# H18R11.net
KiCad netlist of a schematic drawn in EAGLE
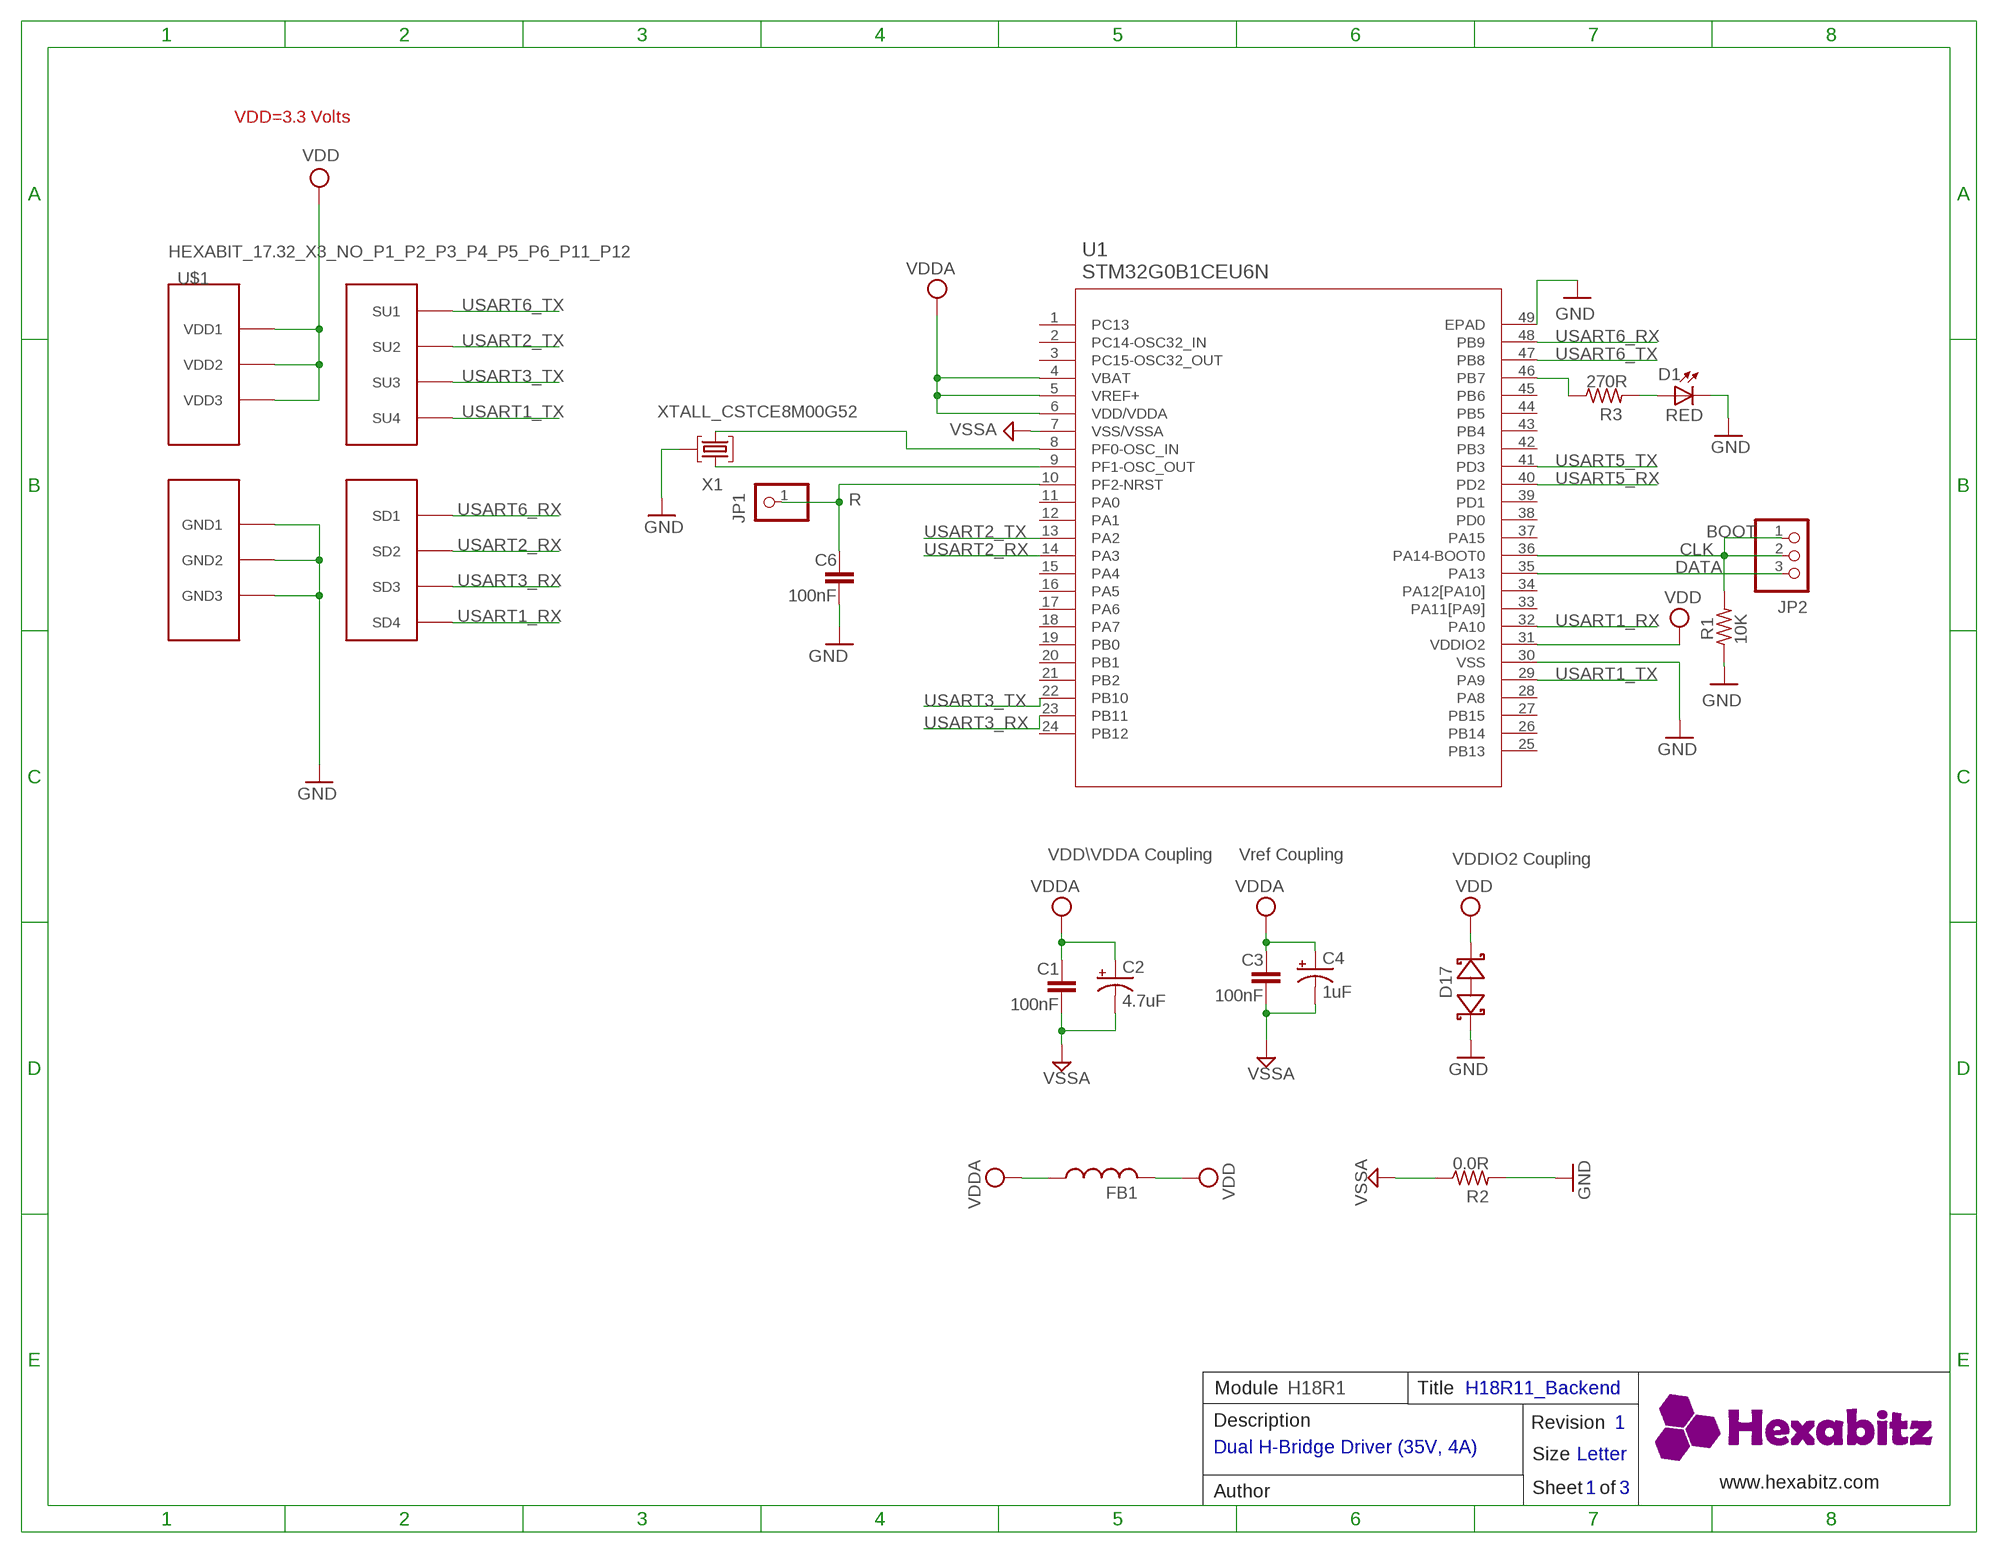
[diagram p0: schematic, sheet 1]
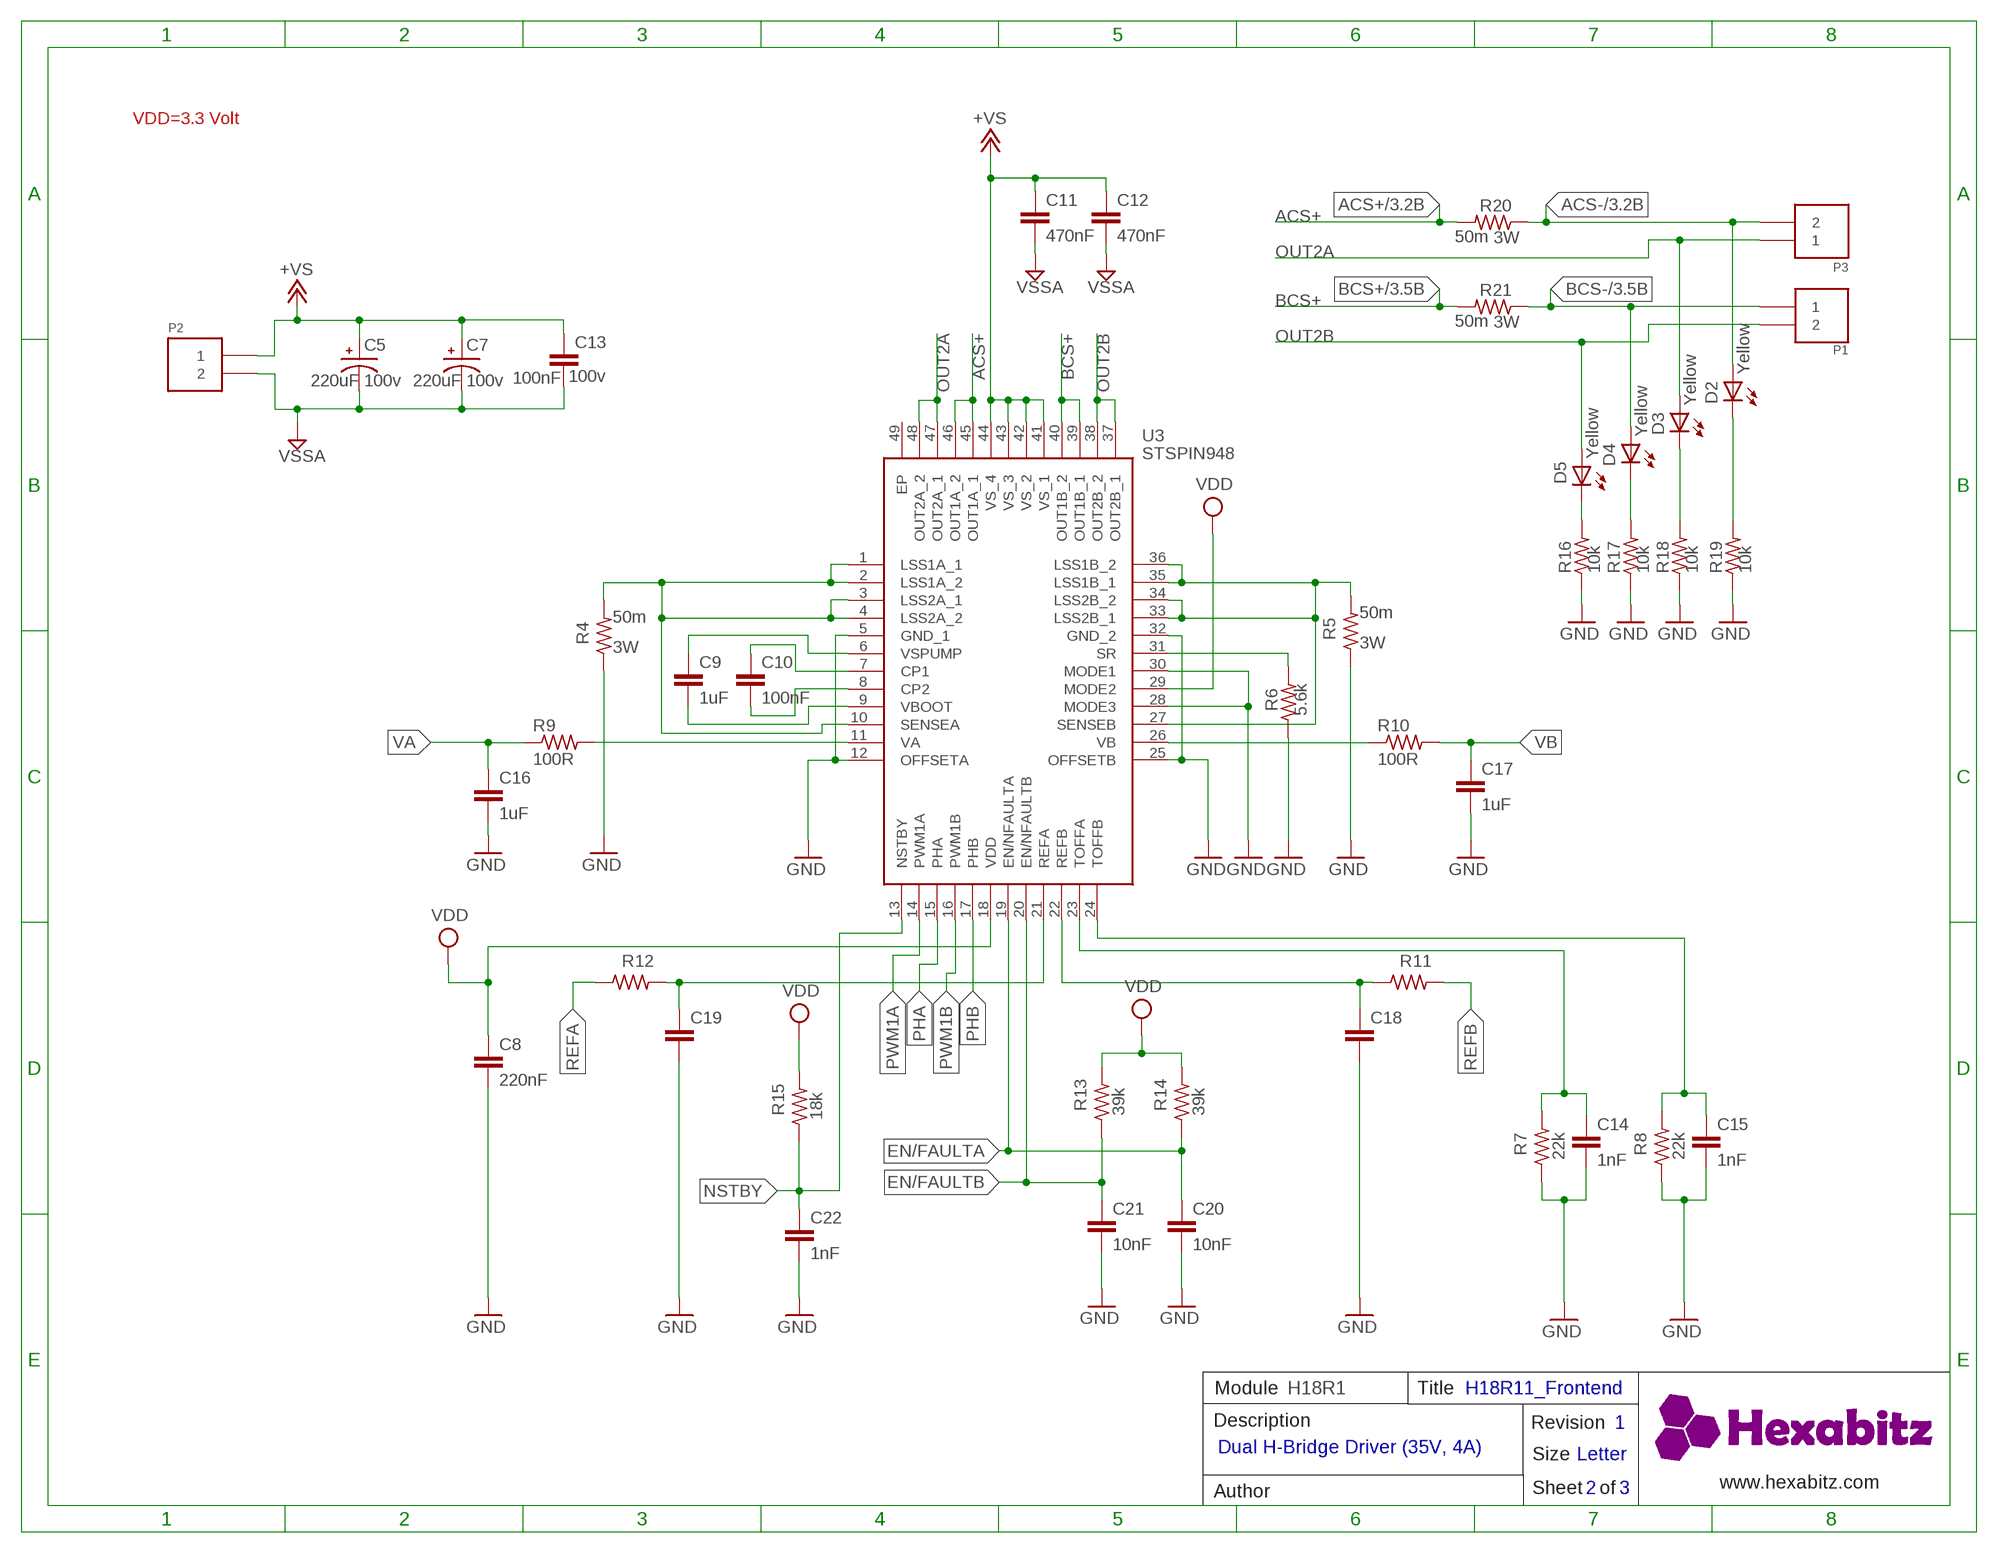
[diagram p1: schematic, sheet 2]
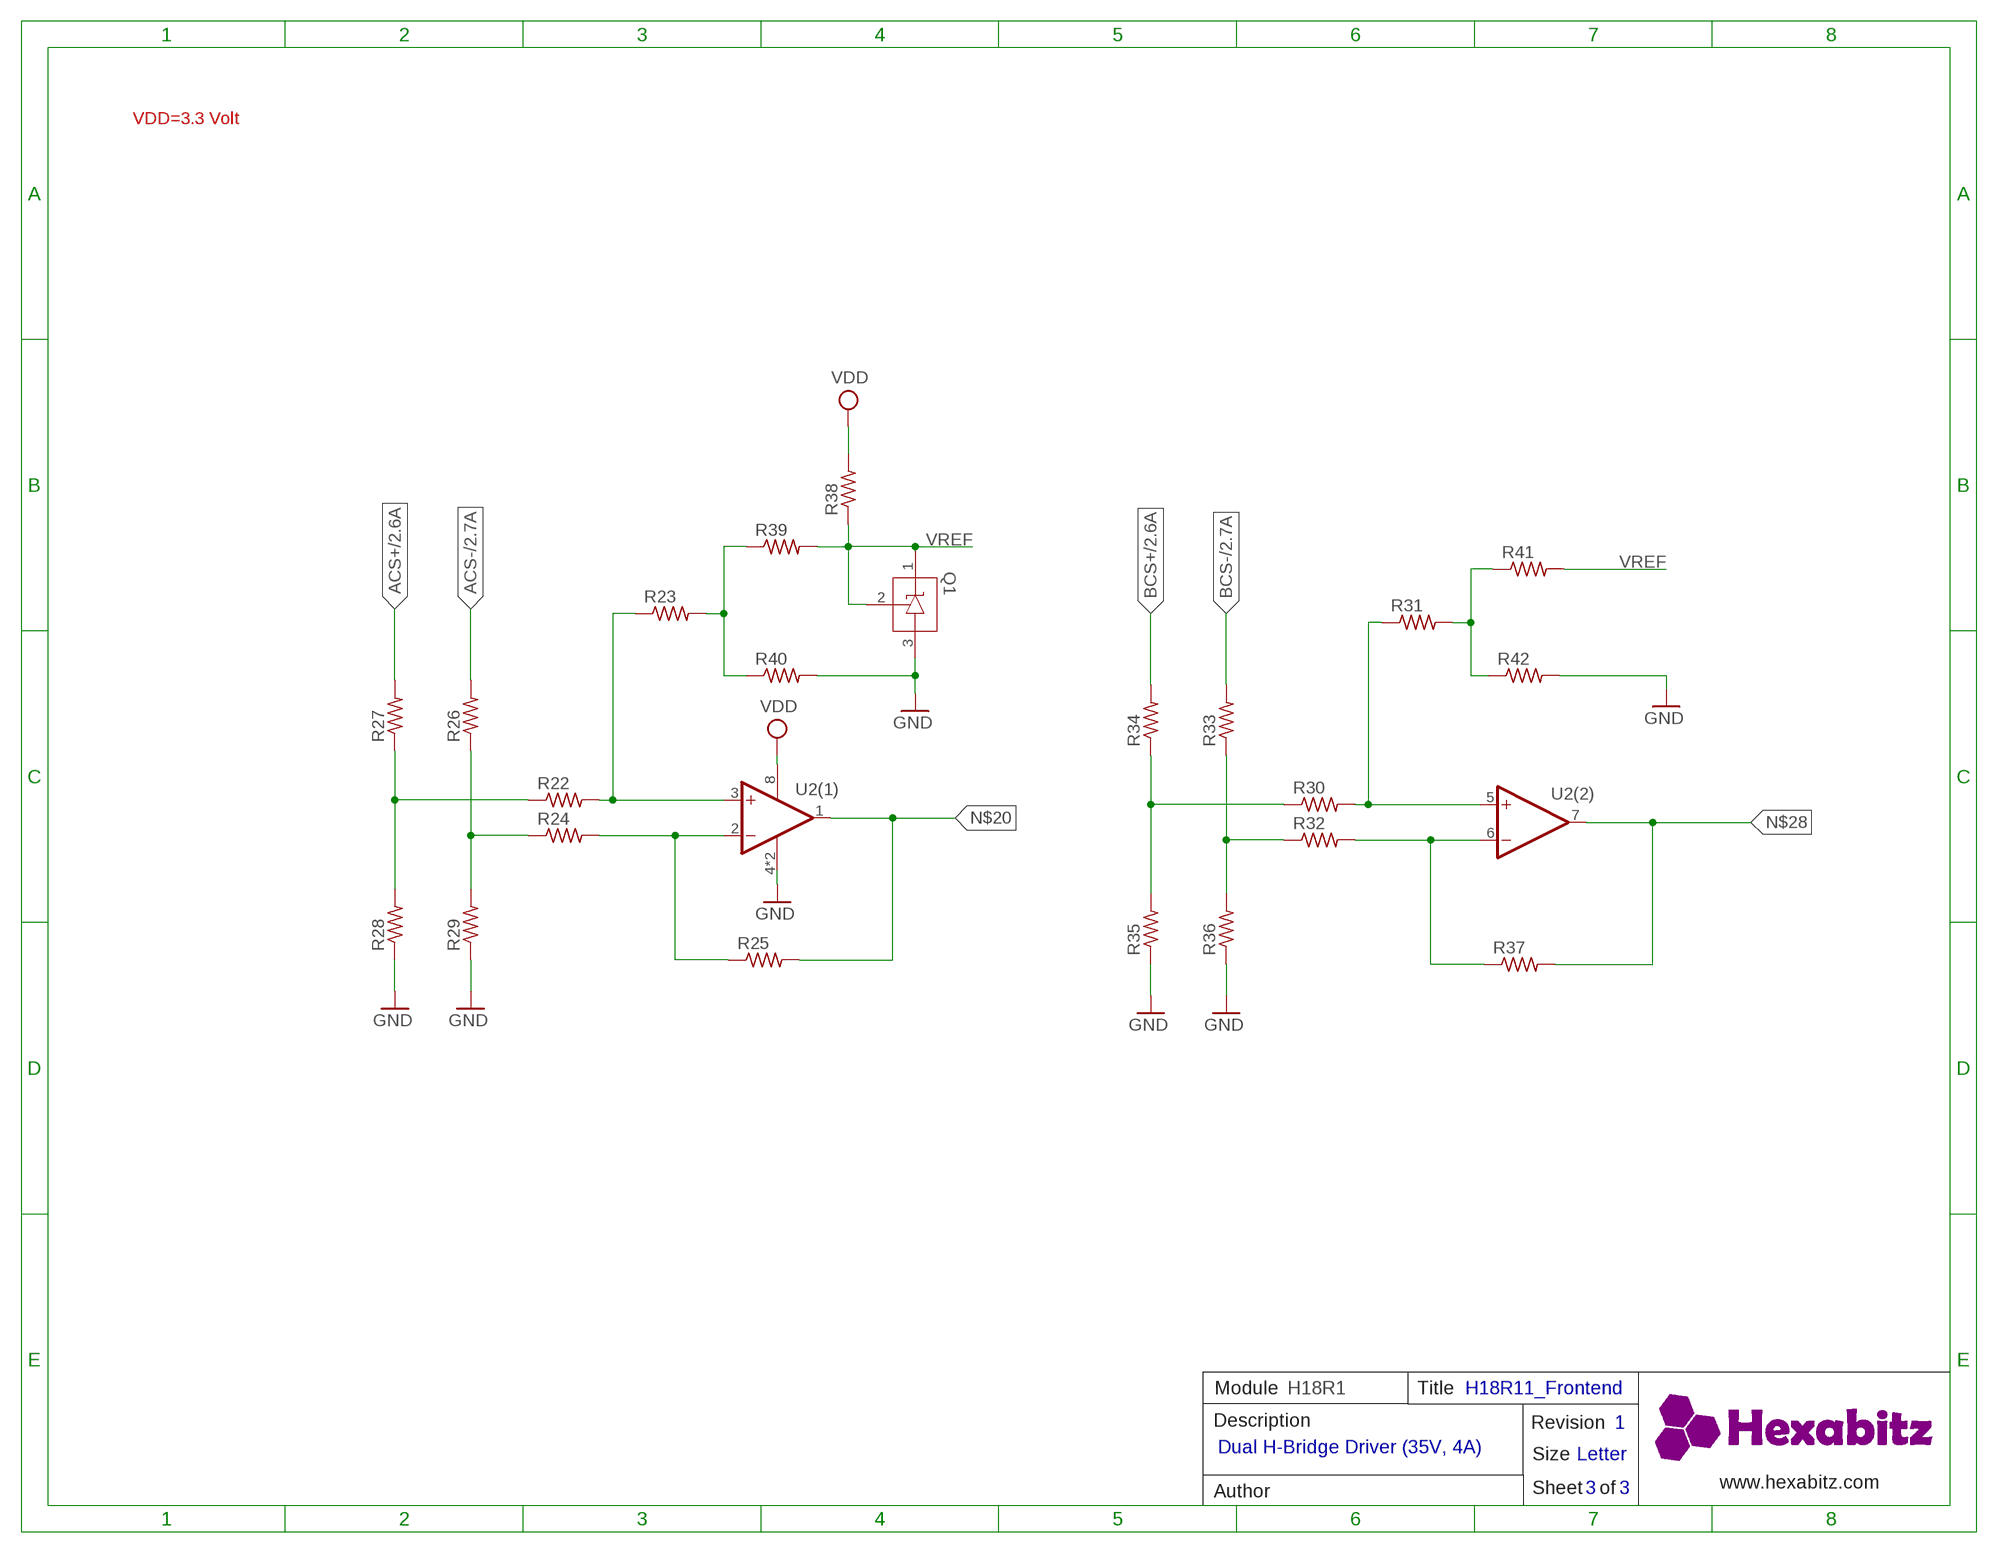
[diagram p2: schematic, sheet 3]

(export (version "E")
  (design (tool "Eeschema 10.0.6"))
  (components
    (comp (ref "Q1")
      (value "TL431QDBZR,215")
      (footprint "eagle-import:SOT23_TO-236AB_NEX")
      (fields (field (name "COPYRIGHT") "Copyright (C) 2022 Ultra Librarian. All rights reserved."))
      (libsource (lib "eagle-import") (part "TL431QDBZR,215"))
    )
    (comp (ref "R22")
      (value "R-0402")
      (footprint "eagle-import:R-0402")
      (libsource (lib "eagle-import") (part "R-0402"))
    )
    (comp (ref "R23")
      (value "R-0402")
      (footprint "eagle-import:R-0402")
      (libsource (lib "eagle-import") (part "R-0402"))
    )
    (comp (ref "R24")
      (value "R-0402")
      (footprint "eagle-import:R-0402")
      (libsource (lib "eagle-import") (part "R-0402"))
    )
    (comp (ref "R25")
      (value "R-0402")
      (footprint "eagle-import:R-0402")
      (libsource (lib "eagle-import") (part "R-0402"))
    )
    (comp (ref "R26")
      (value "R-0402")
      (footprint "eagle-import:R-0402")
      (libsource (lib "eagle-import") (part "R-0402"))
    )
    (comp (ref "R27")
      (value "R-0402")
      (footprint "eagle-import:R-0402")
      (libsource (lib "eagle-import") (part "R-0402"))
    )
    (comp (ref "R28")
      (value "R-0402")
      (footprint "eagle-import:R-0402")
      (libsource (lib "eagle-import") (part "R-0402"))
    )
    (comp (ref "R29")
      (value "R-0402")
      (footprint "eagle-import:R-0402")
      (libsource (lib "eagle-import") (part "R-0402"))
    )
    (comp (ref "R30")
      (value "R-0402")
      (footprint "eagle-import:R-0402")
      (libsource (lib "eagle-import") (part "R-0402"))
    )
    (comp (ref "R31")
      (value "R-0402")
      (footprint "eagle-import:R-0402")
      (libsource (lib "eagle-import") (part "R-0402"))
    )
    (comp (ref "R32")
      (value "R-0402")
      (footprint "eagle-import:R-0402")
      (libsource (lib "eagle-import") (part "R-0402"))
    )
    (comp (ref "R33")
      (value "R-0402")
      (footprint "eagle-import:R-0402")
      (libsource (lib "eagle-import") (part "R-0402"))
    )
    (comp (ref "R34")
      (value "R-0402")
      (footprint "eagle-import:R-0402")
      (libsource (lib "eagle-import") (part "R-0402"))
    )
    (comp (ref "R35")
      (value "R-0402")
      (footprint "eagle-import:R-0402")
      (libsource (lib "eagle-import") (part "R-0402"))
    )
    (comp (ref "R36")
      (value "R-0402")
      (footprint "eagle-import:R-0402")
      (libsource (lib "eagle-import") (part "R-0402"))
    )
    (comp (ref "R37")
      (value "R-0402")
      (footprint "eagle-import:R-0402")
      (libsource (lib "eagle-import") (part "R-0402"))
    )
    (comp (ref "R38")
      (value "R-0402")
      (footprint "eagle-import:R-0402")
      (libsource (lib "eagle-import") (part "R-0402"))
    )
    (comp (ref "R39")
      (value "R-0402")
      (footprint "eagle-import:R-0402")
      (libsource (lib "eagle-import") (part "R-0402"))
    )
    (comp (ref "R40")
      (value "R-0402")
      (footprint "eagle-import:R-0402")
      (libsource (lib "eagle-import") (part "R-0402"))
    )
    (comp (ref "R41")
      (value "R-0402")
      (footprint "eagle-import:R-0402")
      (libsource (lib "eagle-import") (part "R-0402"))
    )
    (comp (ref "R42")
      (value "R-0402")
      (footprint "eagle-import:R-0402")
      (libsource (lib "eagle-import") (part "R-0402"))
    )
    (comp (ref "U2")
      (value "TSV772IQ2T_SEPARATED_SYMBOLSSON50P200X200X60-9N")
      (footprint "eagle-import:SON50P200X200X60-9N")
      (libsource (lib "eagle-import") (part "TSV772IQ2T_SEPARATED_SYMBOLSSON50P200X200X60-9N"))
    )
    (comp (ref "C1")
      (value "100nF")
      (footprint "eagle-import:C-0603")
      (libsource (lib "eagle-import") (part "C-0603"))
    )
    (comp (ref "C2")
      (value "4.7uF")
      (footprint "eagle-import:C-0805-POL")
      (libsource (lib "eagle-import") (part "C-0805-POL"))
    )
    (comp (ref "C3")
      (value "100nF")
      (footprint "eagle-import:C-0603")
      (libsource (lib "eagle-import") (part "C-0603"))
    )
    (comp (ref "C4")
      (value "1uF")
      (footprint "eagle-import:C-0805-POL")
      (libsource (lib "eagle-import") (part "C-0805-POL"))
    )
    (comp (ref "C6")
      (value "100nF")
      (footprint "eagle-import:C-0603")
      (libsource (lib "eagle-import") (part "C-0603"))
    )
    (comp (ref "D1")
      (value "RED")
      (footprint "eagle-import:VLMS1300-GS08")
      (fields
        (field (name "MPN") "VLMS1300-GS08")
        (field (name "MFN") "Vishay")
        (field (name "MPN_1") "VLMS1300-GS08")
        (field (name "OCTOPART_URL") "https://octopart.com/vlms1300-gs08-vishay-21709201?r=sp&s=_gcP4_q8T1SC6PJQPTQ9yA")
      )
      (libsource (lib "eagle-import") (part "VLMS1300-GS08"))
    )
    (comp (ref "D17")
      (value "BOURNS_CDSOD323-T03SCBOURNS_CDSOD323-T03SC_0_0")
      (footprint "eagle-import:BOURNS_CDSOD323-T03SC_0")
      (fields (field (name "MPN") "CDSOD323-T03SC"))
      (libsource (lib "eagle-import") (part "BOURNS_CDSOD323-T03SCBOURNS_CDSOD323-T03SC_0_0"))
    )
    (comp (ref "FB1")
      (value "FB-0603")
      (footprint "eagle-import:FB-0603")
      (libsource (lib "eagle-import") (part "FB-0603"))
    )
    (comp (ref "JP1")
      (value "R")
      (footprint "eagle-import:1X01")
      (fields (field (name "MPN") "87227-1"))
      (libsource (lib "eagle-import") (part "PINHD-1X1"))
    )
    (comp (ref "JP2")
      (value "PINHD-1X3")
      (footprint "eagle-import:1X03")
      (libsource (lib "eagle-import") (part "PINHD-1X3"))
    )
    (comp (ref "R1")
      (value "10K")
      (footprint "eagle-import:R-0603")
      (libsource (lib "eagle-import") (part "R-0603"))
    )
    (comp (ref "R2")
      (value "0.0R")
      (footprint "eagle-import:R-0603")
      (libsource (lib "eagle-import") (part "R-0603"))
    )
    (comp (ref "R3")
      (value "270R")
      (footprint "eagle-import:R-0603")
      (libsource (lib "eagle-import") (part "R-0603"))
    )
    (comp (ref "U$1")
      (value "HEXABIT_17.32_X3_NO_P1_P2_P3_P4_P5_P6_P11_P12")
      (footprint "eagle-import:HEXABIT_17.32_X3_NO_P1_P2_P3_P4_P5_P6_P11_P12")
      (libsource (lib "eagle-import") (part "HEXABIT_17.32_X3_NO_P1_P2_P3_P4_P5_P6_P11_P12"))
    )
    (comp (ref "U1")
      (value "STM32G0B1CEU6N")
      (footprint "eagle-import:HEXABITZ_ICS_QFN_B1CEU6_STM-L")
      (libsource (lib "eagle-import") (part "STM32G0B1CEU6N"))
    )
    (comp (ref "X1")
      (value "XTALL_CSTCE8M00G52")
      (footprint "eagle-import:XTALL_CSTCE8M00G52")
      (fields (field (name "MPN") "CSTCE8M00G52Z-R0"))
      (libsource (lib "eagle-import") (part "XTALL_CSTCE8M00G52"))
    )
    (comp (ref "C5")
      (value "220uF")
      (footprint "eagle-import:CAPPRD500W60D1250H2500")
      (fields
        (field (name "MF") "Panasonic Electronic Components")
        (field (name "MP") "EEU-FS2A221B")
        (field (name "VOLT") "100v")
      )
      (libsource (lib "eagle-import") (part "EEUFS2A221B"))
    )
    (comp (ref "C7")
      (value "220uF")
      (footprint "eagle-import:CAPPRD500W60D1250H2500")
      (fields
        (field (name "MF") "Panasonic Electronic Components")
        (field (name "MP") "EEU-FS2A221B")
        (field (name "VOLT") "100v")
      )
      (libsource (lib "eagle-import") (part "EEUFS2A221B"))
    )
    (comp (ref "C8")
      (value "220nF")
      (footprint "eagle-import:C-0603")
      (libsource (lib "eagle-import") (part "C-0603"))
    )
    (comp (ref "C9")
      (value "1uF")
      (footprint "eagle-import:C-0603")
      (libsource (lib "eagle-import") (part "C-0603"))
    )
    (comp (ref "C10")
      (value "100nF")
      (footprint "eagle-import:C-0603")
      (libsource (lib "eagle-import") (part "C-0603"))
    )
    (comp (ref "C11")
      (value "470nF")
      (footprint "eagle-import:C-0603")
      (libsource (lib "eagle-import") (part "C-0603"))
    )
    (comp (ref "C12")
      (value "470nF")
      (footprint "eagle-import:C-0603")
      (libsource (lib "eagle-import") (part "C-0603"))
    )
    (comp (ref "C13")
      (value "100nF")
      (footprint "eagle-import:C-0603")
      (fields (field (name "VOLTAGE_RATING") "100v"))
      (libsource (lib "eagle-import") (part "C-0603"))
    )
    (comp (ref "C14")
      (value "1nF")
      (footprint "eagle-import:C-0603")
      (libsource (lib "eagle-import") (part "C-0603"))
    )
    (comp (ref "C15")
      (value "1nF")
      (footprint "eagle-import:C-0603")
      (libsource (lib "eagle-import") (part "C-0603"))
    )
    (comp (ref "C16")
      (value "1uF")
      (footprint "eagle-import:C-0603")
      (libsource (lib "eagle-import") (part "C-0603"))
    )
    (comp (ref "C17")
      (value "1uF")
      (footprint "eagle-import:C-0603")
      (libsource (lib "eagle-import") (part "C-0603"))
    )
    (comp (ref "C18")
      (value "C-0603")
      (footprint "eagle-import:C-0603")
      (libsource (lib "eagle-import") (part "C-0603"))
    )
    (comp (ref "C19")
      (value "C-0603")
      (footprint "eagle-import:C-0603")
      (libsource (lib "eagle-import") (part "C-0603"))
    )
    (comp (ref "C20")
      (value "10nF")
      (footprint "eagle-import:C-0603")
      (libsource (lib "eagle-import") (part "C-0603"))
    )
    (comp (ref "C21")
      (value "10nF")
      (footprint "eagle-import:C-0603")
      (libsource (lib "eagle-import") (part "C-0603"))
    )
    (comp (ref "C22")
      (value "1nF")
      (footprint "eagle-import:C-0603")
      (libsource (lib "eagle-import") (part "C-0603"))
    )
    (comp (ref "D2")
      (value "Yellow")
      (footprint "eagle-import:VLMS1300-GS08")
      (fields
        (field (name "MPN") "VLMS1300-GS08")
        (field (name "MFN") "Vishay")
        (field (name "MPN_1") "VLMS1300-GS08")
        (field (name "OCTOPART_URL") "https://octopart.com/vlms1300-gs08-vishay-21709201?r=sp&s=_gcP4_q8T1SC6PJQPTQ9yA")
      )
      (libsource (lib "eagle-import") (part "VLMS1300-GS08"))
    )
    (comp (ref "D3")
      (value "Yellow")
      (footprint "eagle-import:VLMS1300-GS08")
      (fields
        (field (name "MPN") "VLMS1300-GS08")
        (field (name "OCTOPART_URL") "https://octopart.com/vlms1300-gs08-vishay-21709201?r=sp&s=_gcP4_q8T1SC6PJQPTQ9yA")
      )
      (libsource (lib "eagle-import") (part "VLMS1300-GS08"))
    )
    (comp (ref "D4")
      (value "Yellow")
      (footprint "eagle-import:VLMS1300-GS08")
      (fields
        (field (name "MPN") "VLMS1300-GS08")
        (field (name "OCTOPART_URL") "https://octopart.com/vlms1300-gs08-vishay-21709201?r=sp&s=_gcP4_q8T1SC6PJQPTQ9yA")
      )
      (libsource (lib "eagle-import") (part "VLMS1300-GS08"))
    )
    (comp (ref "D5")
      (value "Yellow")
      (footprint "eagle-import:VLMS1300-GS08")
      (fields
        (field (name "MPN") "VLMS1300-GS08")
        (field (name "OCTOPART_URL") "https://octopart.com/vlms1300-gs08-vishay-21709201?r=sp&s=_gcP4_q8T1SC6PJQPTQ9yA")
      )
      (libsource (lib "eagle-import") (part "VLMS1300-GS08"))
    )
    (comp (ref "P1")
      (value "1546111-2")
      (footprint "eagle-import:1546111-2")
      (libsource (lib "eagle-import") (part "1546111-2"))
    )
    (comp (ref "P2")
      (value "1546111-2")
      (footprint "eagle-import:1546111-2")
      (libsource (lib "eagle-import") (part "1546111-2"))
    )
    (comp (ref "P3")
      (value "1546111-2")
      (footprint "eagle-import:1546111-2")
      (libsource (lib "eagle-import") (part "1546111-2"))
    )
    (comp (ref "R4")
      (value "50m")
      (footprint "eagle-import:R2512")
      (fields (field (name "MPN") "CRA2512-FZ-R050ELF ") (field (name "POWER") "3W"))
      (libsource (lib "eagle-import") (part "R-US_R2512"))
    )
    (comp (ref "R5")
      (value "50m")
      (footprint "eagle-import:R2512")
      (fields (field (name "MPN") "CRA2512-FZ-R050ELF ") (field (name "POWER") "3W"))
      (libsource (lib "eagle-import") (part "R-US_R2512"))
    )
    (comp (ref "R6")
      (value "5.6k")
      (footprint "eagle-import:R-0603")
      (libsource (lib "eagle-import") (part "R-0603"))
    )
    (comp (ref "R7")
      (value "22k")
      (footprint "eagle-import:R-0603")
      (libsource (lib "eagle-import") (part "R-0603"))
    )
    (comp (ref "R8")
      (value "22k")
      (footprint "eagle-import:R-0603")
      (libsource (lib "eagle-import") (part "R-0603"))
    )
    (comp (ref "R9")
      (value "100R")
      (footprint "eagle-import:R-0603")
      (libsource (lib "eagle-import") (part "R-0603"))
    )
    (comp (ref "R10")
      (value "100R")
      (footprint "eagle-import:R-0603")
      (libsource (lib "eagle-import") (part "R-0603"))
    )
    (comp (ref "R11")
      (value "R-0603")
      (footprint "eagle-import:R-0603")
      (libsource (lib "eagle-import") (part "R-0603"))
    )
    (comp (ref "R12")
      (value "R-0603")
      (footprint "eagle-import:R-0603")
      (libsource (lib "eagle-import") (part "R-0603"))
    )
    (comp (ref "R13")
      (value "39k")
      (footprint "eagle-import:R-0603")
      (libsource (lib "eagle-import") (part "R-0603"))
    )
    (comp (ref "R14")
      (value "39k")
      (footprint "eagle-import:R-0603")
      (libsource (lib "eagle-import") (part "R-0603"))
    )
    (comp (ref "R15")
      (value "18k")
      (footprint "eagle-import:R-0603")
      (libsource (lib "eagle-import") (part "R-0603"))
    )
    (comp (ref "R16")
      (value "10k")
      (footprint "eagle-import:R-0805")
      (libsource (lib "eagle-import") (part "R-0805"))
    )
    (comp (ref "R17")
      (value "10k")
      (footprint "eagle-import:R-0805")
      (libsource (lib "eagle-import") (part "R-0805"))
    )
    (comp (ref "R18")
      (value "10k")
      (footprint "eagle-import:R-0805")
      (libsource (lib "eagle-import") (part "R-0805"))
    )
    (comp (ref "R19")
      (value "10k")
      (footprint "eagle-import:R-0805")
      (libsource (lib "eagle-import") (part "R-0805"))
    )
    (comp (ref "R20")
      (value "50m")
      (footprint "eagle-import:R2512")
      (fields (field (name "MPN") "CRA2512-FZ-R050ELF ") (field (name "POWER") "3W"))
      (libsource (lib "eagle-import") (part "R-US_R2512"))
    )
    (comp (ref "R21")
      (value "50m")
      (footprint "eagle-import:R2512")
      (fields (field (name "MPN") "CRA2512-FZ-R050ELF ") (field (name "POWER") "3W"))
      (libsource (lib "eagle-import") (part "R-US_R2512"))
    )
    (comp (ref "U3")
      (value "STSPIN948")
      (footprint "eagle-import:QFN50P700X700X105-49N")
      (fields (field (name "MOUSER_PART_NUMBER") "511-STSPIN948"))
      (libsource (lib "eagle-import") (part "STSPIN948"))
    )
  )
  (nets
    (net (code "1") (name "+VS") (class "Default")
      (node (ref "C11") (pin "1") (pinfunction "1_1") (pintype "passive"))
      (node (ref "C12") (pin "1") (pinfunction "1_1") (pintype "passive"))
      (node (ref "C13") (pin "1") (pinfunction "1_1") (pintype "passive"))
      (node (ref "C5") (pin "P") (pinfunction "P_P") (pintype "passive"))
      (node (ref "C7") (pin "P") (pinfunction "P_P") (pintype "passive"))
      (node (ref "P2") (pin "1") (pinfunction "1_1") (pintype "power_in"))
      (node (ref "U3") (pin "41") (pinfunction "VS_1_41") (pintype "bidirectional"))
      (node (ref "U3") (pin "42") (pinfunction "VS_2_42") (pintype "bidirectional"))
      (node (ref "U3") (pin "43") (pinfunction "VS_3_43") (pintype "bidirectional"))
      (node (ref "U3") (pin "44") (pinfunction "VS_4_44") (pintype "bidirectional"))
    )
    (net (code "2") (name "ACS+") (class "Default")
      (node (ref "R20") (pin "2") (pinfunction "2_2") (pintype "passive"))
      (node (ref "R27") (pin "2") (pinfunction "2_2") (pintype "passive"))
      (node (ref "U3") (pin "45") (pinfunction "OUT1A_1_45") (pintype "bidirectional"))
      (node (ref "U3") (pin "46") (pinfunction "OUT1A_2_46") (pintype "bidirectional"))
    )
    (net (code "3") (name "ACS-") (class "Default")
      (node (ref "D2") (pin "A") (pinfunction "A_A") (pintype "passive"))
      (node (ref "P3") (pin "2") (pinfunction "2_2") (pintype "power_in"))
      (node (ref "R20") (pin "1") (pinfunction "1_1") (pintype "passive"))
      (node (ref "R26") (pin "2") (pinfunction "2_2") (pintype "passive"))
    )
    (net (code "4") (name "BCS+") (class "Default")
      (node (ref "R21") (pin "2") (pinfunction "2_2") (pintype "passive"))
      (node (ref "R34") (pin "2") (pinfunction "2_2") (pintype "passive"))
      (node (ref "U3") (pin "39") (pinfunction "OUT1B_1_39") (pintype "bidirectional"))
      (node (ref "U3") (pin "40") (pinfunction "OUT1B_2_40") (pintype "bidirectional"))
    )
    (net (code "5") (name "BCS-") (class "Default")
      (node (ref "D4") (pin "A") (pinfunction "A_A") (pintype "passive"))
      (node (ref "P1") (pin "1") (pinfunction "1_1") (pintype "power_in"))
      (node (ref "R21") (pin "1") (pinfunction "1_1") (pintype "passive"))
      (node (ref "R33") (pin "2") (pinfunction "2_2") (pintype "passive"))
    )
    (net (code "6") (name "CLK") (class "Default")
      (node (ref "JP2") (pin "1") (pinfunction "1_1") (pintype "passive"))
      (node (ref "JP2") (pin "2") (pinfunction "2_2") (pintype "passive"))
      (node (ref "R1") (pin "2") (pinfunction "2_2") (pintype "passive"))
      (node (ref "U1") (pin "36") (pinfunction "PA14-BOOT0_36") (pintype "bidirectional"))
    )
    (net (code "7") (name "DATA") (class "Default")
      (node (ref "JP2") (pin "3") (pinfunction "3_3") (pintype "passive"))
      (node (ref "U1") (pin "35") (pinfunction "PA13_35") (pintype "bidirectional"))
    )
    (net (code "8") (name "EN{slash}FAULTA") (class "Default")
      (node (ref "C20") (pin "1") (pinfunction "1_1") (pintype "passive"))
      (node (ref "R14") (pin "1") (pinfunction "1_1") (pintype "passive"))
      (node (ref "U3") (pin "19") (pinfunction "EN/NFAULTA_19") (pintype "bidirectional"))
    )
    (net (code "9") (name "EN{slash}FAULTB") (class "Default")
      (node (ref "C21") (pin "1") (pinfunction "1_1") (pintype "passive"))
      (node (ref "R13") (pin "1") (pinfunction "1_1") (pintype "passive"))
      (node (ref "U3") (pin "20") (pinfunction "EN/NFAULTB_20") (pintype "bidirectional"))
    )
    (net (code "10") (name "GND") (class "Default")
      (node (ref "C14") (pin "2") (pinfunction "2_2") (pintype "passive"))
      (node (ref "C15") (pin "2") (pinfunction "2_2") (pintype "passive"))
      (node (ref "C16") (pin "2") (pinfunction "2_2") (pintype "passive"))
      (node (ref "C17") (pin "2") (pinfunction "2_2") (pintype "passive"))
      (node (ref "C18") (pin "2") (pinfunction "2_2") (pintype "passive"))
      (node (ref "C19") (pin "2") (pinfunction "2_2") (pintype "passive"))
      (node (ref "C20") (pin "2") (pinfunction "2_2") (pintype "passive"))
      (node (ref "C21") (pin "2") (pinfunction "2_2") (pintype "passive"))
      (node (ref "C22") (pin "2") (pinfunction "2_2") (pintype "passive"))
      (node (ref "C6") (pin "2") (pinfunction "2_2") (pintype "passive"))
      (node (ref "C8") (pin "2") (pinfunction "2_2") (pintype "passive"))
      (node (ref "D1") (pin "C") (pinfunction "C_C") (pintype "passive"))
      (node (ref "D17") (pin "1") (pinfunction "A_1") (pintype "passive"))
      (node (ref "Q1") (pin "3") (pinfunction "3_3") (pintype "passive"))
      (node (ref "R1") (pin "1") (pinfunction "1_1") (pintype "passive"))
      (node (ref "R16") (pin "1") (pinfunction "1_1") (pintype "passive"))
      (node (ref "R17") (pin "1") (pinfunction "1_1") (pintype "passive"))
      (node (ref "R18") (pin "1") (pinfunction "1_1") (pintype "passive"))
      (node (ref "R19") (pin "1") (pinfunction "1_1") (pintype "passive"))
      (node (ref "R2") (pin "2") (pinfunction "2_2") (pintype "passive"))
      (node (ref "R28") (pin "1") (pinfunction "1_1") (pintype "passive"))
      (node (ref "R29") (pin "1") (pinfunction "1_1") (pintype "passive"))
      (node (ref "R35") (pin "1") (pinfunction "1_1") (pintype "passive"))
      (node (ref "R36") (pin "1") (pinfunction "1_1") (pintype "passive"))
      (node (ref "R4") (pin "1") (pinfunction "1_1") (pintype "passive"))
      (node (ref "R40") (pin "2") (pinfunction "2_2") (pintype "passive"))
      (node (ref "R42") (pin "2") (pinfunction "2_2") (pintype "passive"))
      (node (ref "R5") (pin "1") (pinfunction "1_1") (pintype "passive"))
      (node (ref "R6") (pin "1") (pinfunction "1_1") (pintype "passive"))
      (node (ref "R7") (pin "1") (pinfunction "1_1") (pintype "passive"))
      (node (ref "R8") (pin "1") (pinfunction "1_1") (pintype "passive"))
      (node (ref "U$1") (pin "PAD_PD12") (pinfunction "GND1_PAD_PD12") (pintype "power_in"))
      (node (ref "U$1") (pin "PAD_PD17") (pinfunction "GND2_PAD_PD17") (pintype "power_in"))
      (node (ref "U$1") (pin "PAD_PD19") (pinfunction "GND3_PAD_PD19") (pintype "power_in"))
      (node (ref "U1") (pin "30") (pinfunction "VSS_30") (pintype "passive"))
      (node (ref "U1") (pin "49") (pinfunction "EPAD_49") (pintype "passive"))
      (node (ref "U2") (pin "4") (pinfunction "V-_4") (pintype "power_in"))
      (node (ref "U2") (pin "9") (pinfunction "V-_9") (pintype "power_in"))
      (node (ref "U3") (pin "12") (pinfunction "OFFSETA_12") (pintype "bidirectional"))
      (node (ref "U3") (pin "25") (pinfunction "OFFSETB_25") (pintype "bidirectional"))
      (node (ref "U3") (pin "28") (pinfunction "MODE3_28") (pintype "bidirectional"))
      (node (ref "U3") (pin "30") (pinfunction "MODE1_30") (pintype "bidirectional"))
      (node (ref "U3") (pin "32") (pinfunction "GND_2_32") (pintype "bidirectional"))
      (node (ref "U3") (pin "5") (pinfunction "GND_1_5") (pintype "bidirectional"))
      (node (ref "X1") (pin "P$2") (pinfunction "2_P$2") (pintype "passive"))
    )
    (net (code "11") (name "N$20") (class "Default")
      (node (ref "R25") (pin "2") (pinfunction "2_2") (pintype "passive"))
      (node (ref "U2") (pin "1") (pinfunction "OUT_1") (pintype "output"))
    )
    (net (code "12") (name "N$28") (class "Default")
      (node (ref "R37") (pin "2") (pinfunction "2_2") (pintype "passive"))
      (node (ref "U2") (pin "7") (pinfunction "OUT_7") (pintype "output"))
    )
    (net (code "13") (name "NSTBY") (class "Default")
      (node (ref "C22") (pin "1") (pinfunction "1_1") (pintype "passive"))
      (node (ref "R15") (pin "1") (pinfunction "1_1") (pintype "passive"))
      (node (ref "U3") (pin "13") (pinfunction "NSTBY_13") (pintype "bidirectional"))
    )
    (net (code "14") (name "Net-(D1-PadA)") (class "Default")
      (node (ref "D1") (pin "A") (pinfunction "A_A") (pintype "passive"))
      (node (ref "R3") (pin "2") (pinfunction "2_2") (pintype "passive"))
    )
    (net (code "15") (name "Net-(D2-PadC)") (class "Default")
      (node (ref "D2") (pin "C") (pinfunction "C_C") (pintype "passive"))
      (node (ref "R19") (pin "2") (pinfunction "2_2") (pintype "passive"))
    )
    (net (code "16") (name "Net-(D3-PadC)") (class "Default")
      (node (ref "D3") (pin "C") (pinfunction "C_C") (pintype "passive"))
      (node (ref "R18") (pin "2") (pinfunction "2_2") (pintype "passive"))
    )
    (net (code "17") (name "Net-(D4-PadC)") (class "Default")
      (node (ref "D4") (pin "C") (pinfunction "C_C") (pintype "passive"))
      (node (ref "R17") (pin "2") (pinfunction "2_2") (pintype "passive"))
    )
    (net (code "18") (name "Net-(D5-PadC)") (class "Default")
      (node (ref "D5") (pin "C") (pinfunction "C_C") (pintype "passive"))
      (node (ref "R16") (pin "2") (pinfunction "2_2") (pintype "passive"))
    )
    (net (code "19") (name "Net-(R22-Pad1)") (class "Default")
      (node (ref "R22") (pin "1") (pinfunction "1_1") (pintype "passive"))
      (node (ref "R27") (pin "1") (pinfunction "1_1") (pintype "passive"))
      (node (ref "R28") (pin "2") (pinfunction "2_2") (pintype "passive"))
    )
    (net (code "20") (name "Net-(R23-Pad2)") (class "Default")
      (node (ref "R23") (pin "2") (pinfunction "2_2") (pintype "passive"))
      (node (ref "R39") (pin "1") (pinfunction "1_1") (pintype "passive"))
      (node (ref "R40") (pin "1") (pinfunction "1_1") (pintype "passive"))
    )
    (net (code "21") (name "Net-(R24-Pad1)") (class "Default")
      (node (ref "R24") (pin "1") (pinfunction "1_1") (pintype "passive"))
      (node (ref "R26") (pin "1") (pinfunction "1_1") (pintype "passive"))
      (node (ref "R29") (pin "2") (pinfunction "2_2") (pintype "passive"))
    )
    (net (code "22") (name "Net-(R30-Pad1)") (class "Default")
      (node (ref "R30") (pin "1") (pinfunction "1_1") (pintype "passive"))
      (node (ref "R34") (pin "1") (pinfunction "1_1") (pintype "passive"))
      (node (ref "R35") (pin "2") (pinfunction "2_2") (pintype "passive"))
    )
    (net (code "23") (name "Net-(R31-Pad2)") (class "Default")
      (node (ref "R31") (pin "2") (pinfunction "2_2") (pintype "passive"))
      (node (ref "R41") (pin "1") (pinfunction "1_1") (pintype "passive"))
      (node (ref "R42") (pin "1") (pinfunction "1_1") (pintype "passive"))
    )
    (net (code "24") (name "Net-(R32-Pad1)") (class "Default")
      (node (ref "R32") (pin "1") (pinfunction "1_1") (pintype "passive"))
      (node (ref "R33") (pin "1") (pinfunction "1_1") (pintype "passive"))
      (node (ref "R36") (pin "2") (pinfunction "2_2") (pintype "passive"))
    )
    (net (code "25") (name "Net-(U1-PB7)") (class "Default")
      (node (ref "R3") (pin "1") (pinfunction "1_1") (pintype "passive"))
      (node (ref "U1") (pin "46") (pinfunction "PB7_46") (pintype "bidirectional"))
    )
    (net (code "26") (name "Net-(U1-PF0-OSC_IN)") (class "Default")
      (node (ref "U1") (pin "8") (pinfunction "PF0-OSC_IN_8") (pintype "bidirectional"))
      (node (ref "X1") (pin "P$3") (pinfunction "3_P$3") (pintype "passive"))
    )
    (net (code "27") (name "Net-(U1-PF1-OSC_OUT)") (class "Default")
      (node (ref "U1") (pin "9") (pinfunction "PF1-OSC_OUT_9") (pintype "bidirectional"))
      (node (ref "X1") (pin "P$1") (pinfunction "1_P$1") (pintype "passive"))
    )
    (net (code "28") (name "Net-(U1-PF2-NRST)") (class "Default")
      (node (ref "C6") (pin "1") (pinfunction "1_1") (pintype "passive"))
      (node (ref "JP1") (pin "1") (pinfunction "1_1") (pintype "passive"))
      (node (ref "U1") (pin "10") (pinfunction "PF2-NRST_10") (pintype "bidirectional"))
    )
    (net (code "29") (name "Net-(U2A-+IN)") (class "Default")
      (node (ref "R22") (pin "2") (pinfunction "2_2") (pintype "passive"))
      (node (ref "R23") (pin "1") (pinfunction "1_1") (pintype "passive"))
      (node (ref "U2") (pin "3") (pinfunction "+IN_3") (pintype "input"))
    )
    (net (code "30") (name "Net-(U2A--IN)") (class "Default")
      (node (ref "R24") (pin "2") (pinfunction "2_2") (pintype "passive"))
      (node (ref "R25") (pin "1") (pinfunction "1_1") (pintype "passive"))
      (node (ref "U2") (pin "2") (pinfunction "-IN_2") (pintype "input"))
    )
    (net (code "31") (name "Net-(U2B--IN)") (class "Default")
      (node (ref "R32") (pin "2") (pinfunction "2_2") (pintype "passive"))
      (node (ref "R37") (pin "1") (pinfunction "1_1") (pintype "passive"))
      (node (ref "U2") (pin "6") (pinfunction "-IN_6") (pintype "input"))
    )
    (net (code "32") (name "Net-(U3-CP1)") (class "Default")
      (node (ref "C10") (pin "1") (pinfunction "1_1") (pintype "passive"))
      (node (ref "U3") (pin "7") (pinfunction "CP1_7") (pintype "bidirectional"))
    )
    (net (code "33") (name "Net-(U3-CP2)") (class "Default")
      (node (ref "C10") (pin "2") (pinfunction "2_2") (pintype "passive"))
      (node (ref "U3") (pin "8") (pinfunction "CP2_8") (pintype "bidirectional"))
    )
    (net (code "34") (name "Net-(U3-LSS1A_1)") (class "Default")
      (node (ref "R4") (pin "2") (pinfunction "2_2") (pintype "passive"))
      (node (ref "U3") (pin "1") (pinfunction "LSS1A_1_1") (pintype "bidirectional"))
      (node (ref "U3") (pin "10") (pinfunction "SENSEA_10") (pintype "bidirectional"))
      (node (ref "U3") (pin "2") (pinfunction "LSS1A_2_2") (pintype "bidirectional"))
      (node (ref "U3") (pin "3") (pinfunction "LSS2A_1_3") (pintype "bidirectional"))
      (node (ref "U3") (pin "4") (pinfunction "LSS2A_2_4") (pintype "bidirectional"))
    )
    (net (code "35") (name "Net-(U3-LSS1B_1)") (class "Default")
      (node (ref "R5") (pin "2") (pinfunction "2_2") (pintype "passive"))
      (node (ref "U3") (pin "27") (pinfunction "SENSEB_27") (pintype "bidirectional"))
      (node (ref "U3") (pin "33") (pinfunction "LSS2B_1_33") (pintype "bidirectional"))
      (node (ref "U3") (pin "34") (pinfunction "LSS2B_2_34") (pintype "bidirectional"))
      (node (ref "U3") (pin "35") (pinfunction "LSS1B_1_35") (pintype "bidirectional"))
      (node (ref "U3") (pin "36") (pinfunction "LSS1B_2_36") (pintype "bidirectional"))
    )
    (net (code "36") (name "Net-(U3-REFA)") (class "Default")
      (node (ref "C19") (pin "1") (pinfunction "1_1") (pintype "passive"))
      (node (ref "R12") (pin "2") (pinfunction "2_2") (pintype "passive"))
      (node (ref "U3") (pin "21") (pinfunction "REFA_21") (pintype "bidirectional"))
    )
    (net (code "37") (name "Net-(U3-REFB)") (class "Default")
      (node (ref "C18") (pin "1") (pinfunction "1_1") (pintype "passive"))
      (node (ref "R11") (pin "1") (pinfunction "1_1") (pintype "passive"))
      (node (ref "U3") (pin "22") (pinfunction "REFB_22") (pintype "bidirectional"))
    )
    (net (code "38") (name "Net-(U3-SR)") (class "Default")
      (node (ref "R6") (pin "2") (pinfunction "2_2") (pintype "passive"))
      (node (ref "U3") (pin "31") (pinfunction "SR_31") (pintype "bidirectional"))
    )
    (net (code "39") (name "Net-(U3-TOFFA)") (class "Default")
      (node (ref "C14") (pin "1") (pinfunction "1_1") (pintype "passive"))
      (node (ref "R7") (pin "2") (pinfunction "2_2") (pintype "passive"))
      (node (ref "U3") (pin "23") (pinfunction "TOFFA_23") (pintype "bidirectional"))
    )
    (net (code "40") (name "Net-(U3-TOFFB)") (class "Default")
      (node (ref "C15") (pin "1") (pinfunction "1_1") (pintype "passive"))
      (node (ref "R8") (pin "2") (pinfunction "2_2") (pintype "passive"))
      (node (ref "U3") (pin "24") (pinfunction "TOFFB_24") (pintype "bidirectional"))
    )
    (net (code "41") (name "Net-(U3-VA)") (class "Default")
      (node (ref "R9") (pin "2") (pinfunction "2_2") (pintype "passive"))
      (node (ref "U3") (pin "11") (pinfunction "VA_11") (pintype "bidirectional"))
    )
    (net (code "42") (name "Net-(U3-VB)") (class "Default")
      (node (ref "R10") (pin "1") (pinfunction "1_1") (pintype "passive"))
      (node (ref "U3") (pin "26") (pinfunction "VB_26") (pintype "bidirectional"))
    )
    (net (code "43") (name "Net-(U3-VBOOT)") (class "Default")
      (node (ref "C9") (pin "2") (pinfunction "2_2") (pintype "passive"))
      (node (ref "U3") (pin "9") (pinfunction "VBOOT_9") (pintype "bidirectional"))
    )
    (net (code "44") (name "Net-(U3-VSPUMP)") (class "Default")
      (node (ref "C9") (pin "1") (pinfunction "1_1") (pintype "passive"))
      (node (ref "U3") (pin "6") (pinfunction "VSPUMP_6") (pintype "bidirectional"))
    )
    (net (code "45") (name "OUT2A") (class "Default")
      (node (ref "D3") (pin "A") (pinfunction "A_A") (pintype "passive"))
      (node (ref "P3") (pin "1") (pinfunction "1_1") (pintype "power_in"))
      (node (ref "U3") (pin "47") (pinfunction "OUT2A_1_47") (pintype "bidirectional"))
      (node (ref "U3") (pin "48") (pinfunction "OUT2A_2_48") (pintype "bidirectional"))
    )
    (net (code "46") (name "OUT2B") (class "Default")
      (node (ref "D5") (pin "A") (pinfunction "A_A") (pintype "passive"))
      (node (ref "P1") (pin "2") (pinfunction "2_2") (pintype "power_in"))
      (node (ref "U3") (pin "37") (pinfunction "OUT2B_1_37") (pintype "bidirectional"))
      (node (ref "U3") (pin "38") (pinfunction "OUT2B_2_38") (pintype "bidirectional"))
    )
    (net (code "47") (name "PHA") (class "Default")
      (node (ref "U3") (pin "15") (pinfunction "PHA_15") (pintype "bidirectional"))
    )
    (net (code "48") (name "PHB") (class "Default")
      (node (ref "U3") (pin "17") (pinfunction "PHB_17") (pintype "bidirectional"))
    )
    (net (code "49") (name "PWM1A") (class "Default")
      (node (ref "U3") (pin "14") (pinfunction "PWM1A_14") (pintype "bidirectional"))
    )
    (net (code "50") (name "PWM1B") (class "Default")
      (node (ref "U3") (pin "16") (pinfunction "PWM1B_16") (pintype "bidirectional"))
    )
    (net (code "51") (name "REFA") (class "Default")
      (node (ref "R12") (pin "1") (pinfunction "1_1") (pintype "passive"))
    )
    (net (code "52") (name "REFB") (class "Default")
      (node (ref "R11") (pin "2") (pinfunction "2_2") (pintype "passive"))
    )
    (net (code "53") (name "USART1_RX") (class "Default")
      (node (ref "U$1") (pin "PAD_PD8") (pinfunction "SD4_PAD_PD8") (pintype "bidirectional"))
      (node (ref "U1") (pin "32") (pinfunction "PA10_32") (pintype "bidirectional"))
    )
    (net (code "54") (name "USART1_TX") (class "Default")
      (node (ref "U$1") (pin "PAD_PU8") (pinfunction "SU4_PAD_PU8") (pintype "bidirectional"))
      (node (ref "U1") (pin "29") (pinfunction "PA9_29") (pintype "bidirectional"))
    )
    (net (code "55") (name "USART2_RX") (class "Default")
      (node (ref "U$1") (pin "PAD_PD1") (pinfunction "SD2_PAD_PD1") (pintype "bidirectional"))
      (node (ref "U1") (pin "14") (pinfunction "PA3_14") (pintype "bidirectional"))
    )
    (net (code "56") (name "USART2_TX") (class "Default")
      (node (ref "U$1") (pin "PAD_PU1") (pinfunction "SU2_PAD_PU1") (pintype "bidirectional"))
      (node (ref "U1") (pin "13") (pinfunction "PA2_13") (pintype "bidirectional"))
    )
    (net (code "57") (name "USART3_RX") (class "Default")
      (node (ref "U$1") (pin "PAD_PD2") (pinfunction "SD3_PAD_PD2") (pintype "bidirectional"))
      (node (ref "U1") (pin "23") (pinfunction "PB11_23") (pintype "bidirectional"))
    )
    (net (code "58") (name "USART3_TX") (class "Default")
      (node (ref "U$1") (pin "PAD_PU2") (pinfunction "SU3_PAD_PU2") (pintype "bidirectional"))
      (node (ref "U1") (pin "22") (pinfunction "PB10_22") (pintype "bidirectional"))
    )
    (net (code "59") (name "USART5_RX") (class "Default")
      (node (ref "U1") (pin "40") (pinfunction "PD2_40") (pintype "bidirectional"))
    )
    (net (code "60") (name "USART5_TX") (class "Default")
      (node (ref "U1") (pin "41") (pinfunction "PD3_41") (pintype "bidirectional"))
    )
    (net (code "61") (name "USART6_RX") (class "Default")
      (node (ref "U$1") (pin "PAD_PD3") (pinfunction "SD1_PAD_PD3") (pintype "bidirectional"))
      (node (ref "U1") (pin "48") (pinfunction "PB9_48") (pintype "bidirectional"))
    )
    (net (code "62") (name "USART6_TX") (class "Default")
      (node (ref "U$1") (pin "PAD_PU3") (pinfunction "SU1_PAD_PU3") (pintype "bidirectional"))
      (node (ref "U1") (pin "47") (pinfunction "PB8_47") (pintype "bidirectional"))
    )
    (net (code "63") (name "VA") (class "Default")
      (node (ref "C16") (pin "1") (pinfunction "1_1") (pintype "passive"))
      (node (ref "R9") (pin "1") (pinfunction "1_1") (pintype "passive"))
    )
    (net (code "64") (name "VB") (class "Default")
      (node (ref "C17") (pin "1") (pinfunction "1_1") (pintype "passive"))
      (node (ref "R10") (pin "2") (pinfunction "2_2") (pintype "passive"))
    )
    (net (code "65") (name "VDD") (class "Default")
      (node (ref "C8") (pin "1") (pinfunction "1_1") (pintype "passive"))
      (node (ref "D17") (pin "2") (pinfunction "C_2") (pintype "passive"))
      (node (ref "FB1") (pin "2") (pinfunction "2_2") (pintype "passive"))
      (node (ref "R13") (pin "2") (pinfunction "2_2") (pintype "passive"))
      (node (ref "R14") (pin "2") (pinfunction "2_2") (pintype "passive"))
      (node (ref "R15") (pin "2") (pinfunction "2_2") (pintype "passive"))
      (node (ref "R38") (pin "2") (pinfunction "2_2") (pintype "passive"))
      (node (ref "U$1") (pin "PAD_PU12") (pinfunction "VDD1_PAD_PU12") (pintype "power_in"))
      (node (ref "U$1") (pin "PAD_PU17") (pinfunction "VDD2_PAD_PU17") (pintype "power_in"))
      (node (ref "U$1") (pin "PAD_PU19") (pinfunction "VDD3_PAD_PU19") (pintype "power_in"))
      (node (ref "U1") (pin "31") (pinfunction "VDDIO2_31") (pintype "power_in"))
      (node (ref "U2") (pin "8") (pinfunction "V+_8") (pintype "power_in"))
      (node (ref "U3") (pin "18") (pinfunction "VDD_18") (pintype "bidirectional"))
      (node (ref "U3") (pin "29") (pinfunction "MODE2_29") (pintype "bidirectional"))
    )
    (net (code "66") (name "VDDA") (class "Default")
      (node (ref "C1") (pin "1") (pinfunction "1_1") (pintype "passive"))
      (node (ref "C2") (pin "1") (pinfunction "+_1") (pintype "passive"))
      (node (ref "C3") (pin "1") (pinfunction "1_1") (pintype "passive"))
      (node (ref "C4") (pin "1") (pinfunction "+_1") (pintype "passive"))
      (node (ref "FB1") (pin "1") (pinfunction "1_1") (pintype "passive"))
      (node (ref "U1") (pin "4") (pinfunction "VBAT_4") (pintype "power_in"))
      (node (ref "U1") (pin "5") (pinfunction "VREF+_5") (pintype "power_in"))
      (node (ref "U1") (pin "6") (pinfunction "VDD/VDDA_6") (pintype "power_in"))
    )
    (net (code "67") (name "VREF") (class "Default")
      (node (ref "Q1") (pin "1") (pinfunction "1_1") (pintype "passive"))
      (node (ref "Q1") (pin "2") (pinfunction "2_2") (pintype "passive"))
      (node (ref "R30") (pin "2") (pinfunction "2_2") (pintype "passive"))
      (node (ref "R31") (pin "1") (pinfunction "1_1") (pintype "passive"))
      (node (ref "R38") (pin "1") (pinfunction "1_1") (pintype "passive"))
      (node (ref "R39") (pin "2") (pinfunction "2_2") (pintype "passive"))
      (node (ref "R41") (pin "2") (pinfunction "2_2") (pintype "passive"))
      (node (ref "U2") (pin "5") (pinfunction "+IN_5") (pintype "input"))
    )
    (net (code "68") (name "VSSA") (class "Default")
      (node (ref "C1") (pin "2") (pinfunction "2_2") (pintype "passive"))
      (node (ref "C11") (pin "2") (pinfunction "2_2") (pintype "passive"))
      (node (ref "C12") (pin "2") (pinfunction "2_2") (pintype "passive"))
      (node (ref "C13") (pin "2") (pinfunction "2_2") (pintype "passive"))
      (node (ref "C2") (pin "2") (pinfunction "-_2") (pintype "passive"))
      (node (ref "C3") (pin "2") (pinfunction "2_2") (pintype "passive"))
      (node (ref "C4") (pin "2") (pinfunction "-_2") (pintype "passive"))
      (node (ref "C5") (pin "N") (pinfunction "N_N") (pintype "passive"))
      (node (ref "C7") (pin "N") (pinfunction "N_N") (pintype "passive"))
      (node (ref "P2") (pin "2") (pinfunction "2_2") (pintype "power_in"))
      (node (ref "R2") (pin "1") (pinfunction "1_1") (pintype "passive"))
      (node (ref "U1") (pin "7") (pinfunction "VSS/VSSA_7") (pintype "passive"))
    )
    (net (code "69") (name "unconnected-(U1-PA0-Pad11)") (class "Default")
      (node (ref "U1") (pin "11") (pinfunction "PA0_11") (pintype "bidirectional"))
    )
    (net (code "70") (name "unconnected-(U1-PA1-Pad12)") (class "Default")
      (node (ref "U1") (pin "12") (pinfunction "PA1_12") (pintype "bidirectional"))
    )
    (net (code "71") (name "unconnected-(U1-PA4-Pad15)") (class "Default")
      (node (ref "U1") (pin "15") (pinfunction "PA4_15") (pintype "bidirectional"))
    )
    (net (code "72") (name "unconnected-(U1-PA5-Pad16)") (class "Default")
      (node (ref "U1") (pin "16") (pinfunction "PA5_16") (pintype "bidirectional"))
    )
    (net (code "73") (name "unconnected-(U1-PA6-Pad17)") (class "Default")
      (node (ref "U1") (pin "17") (pinfunction "PA6_17") (pintype "bidirectional"))
    )
    (net (code "74") (name "unconnected-(U1-PA7-Pad18)") (class "Default")
      (node (ref "U1") (pin "18") (pinfunction "PA7_18") (pintype "bidirectional"))
    )
    (net (code "75") (name "unconnected-(U1-PA8-Pad28)") (class "Default")
      (node (ref "U1") (pin "28") (pinfunction "PA8_28") (pintype "bidirectional"))
    )
    (net (code "76") (name "unconnected-(U1-PA11[PA9]-Pad33)") (class "Default")
      (node (ref "U1") (pin "33") (pinfunction "PA11[PA9]_33") (pintype "bidirectional"))
    )
    (net (code "77") (name "unconnected-(U1-PA12[PA10]-Pad34)") (class "Default")
      (node (ref "U1") (pin "34") (pinfunction "PA12[PA10]_34") (pintype "bidirectional"))
    )
    (net (code "78") (name "unconnected-(U1-PA15-Pad37)") (class "Default")
      (node (ref "U1") (pin "37") (pinfunction "PA15_37") (pintype "bidirectional"))
    )
    (net (code "79") (name "unconnected-(U1-PB0-Pad19)") (class "Default")
      (node (ref "U1") (pin "19") (pinfunction "PB0_19") (pintype "bidirectional"))
    )
    (net (code "80") (name "unconnected-(U1-PB1-Pad20)") (class "Default")
      (node (ref "U1") (pin "20") (pinfunction "PB1_20") (pintype "bidirectional"))
    )
    (net (code "81") (name "unconnected-(U1-PB2-Pad21)") (class "Default")
      (node (ref "U1") (pin "21") (pinfunction "PB2_21") (pintype "bidirectional"))
    )
    (net (code "82") (name "unconnected-(U1-PB3-Pad42)") (class "Default")
      (node (ref "U1") (pin "42") (pinfunction "PB3_42") (pintype "bidirectional"))
    )
    (net (code "83") (name "unconnected-(U1-PB4-Pad43)") (class "Default")
      (node (ref "U1") (pin "43") (pinfunction "PB4_43") (pintype "bidirectional"))
    )
    (net (code "84") (name "unconnected-(U1-PB5-Pad44)") (class "Default")
      (node (ref "U1") (pin "44") (pinfunction "PB5_44") (pintype "bidirectional"))
    )
    (net (code "85") (name "unconnected-(U1-PB6-Pad45)") (class "Default")
      (node (ref "U1") (pin "45") (pinfunction "PB6_45") (pintype "bidirectional"))
    )
    (net (code "86") (name "unconnected-(U1-PB12-Pad24)") (class "Default")
      (node (ref "U1") (pin "24") (pinfunction "PB12_24") (pintype "bidirectional"))
    )
    (net (code "87") (name "unconnected-(U1-PB13-Pad25)") (class "Default")
      (node (ref "U1") (pin "25") (pinfunction "PB13_25") (pintype "bidirectional"))
    )
    (net (code "88") (name "unconnected-(U1-PB14-Pad26)") (class "Default")
      (node (ref "U1") (pin "26") (pinfunction "PB14_26") (pintype "bidirectional"))
    )
    (net (code "89") (name "unconnected-(U1-PB15-Pad27)") (class "Default")
      (node (ref "U1") (pin "27") (pinfunction "PB15_27") (pintype "bidirectional"))
    )
    (net (code "90") (name "unconnected-(U1-PC13-Pad1)") (class "Default")
      (node (ref "U1") (pin "1") (pinfunction "PC13_1") (pintype "bidirectional"))
    )
    (net (code "91") (name "unconnected-(U1-PC14-OSC32_IN-Pad2)") (class "Default")
      (node (ref "U1") (pin "2") (pinfunction "PC14-OSC32_IN_2") (pintype "bidirectional"))
    )
    (net (code "92") (name "unconnected-(U1-PC15-OSC32_OUT-Pad3)") (class "Default")
      (node (ref "U1") (pin "3") (pinfunction "PC15-OSC32_OUT_3") (pintype "bidirectional"))
    )
    (net (code "93") (name "unconnected-(U1-PD0-Pad38)") (class "Default")
      (node (ref "U1") (pin "38") (pinfunction "PD0_38") (pintype "bidirectional"))
    )
    (net (code "94") (name "unconnected-(U1-PD1-Pad39)") (class "Default")
      (node (ref "U1") (pin "39") (pinfunction "PD1_39") (pintype "bidirectional"))
    )
    (net (code "95") (name "unconnected-(U3-EP-Pad49)") (class "Default")
      (node (ref "U3") (pin "49") (pinfunction "EP_49") (pintype "bidirectional"))
    )
  )
)
